# openysy.net
KiCad netlist of a schematic drawn in EAGLE
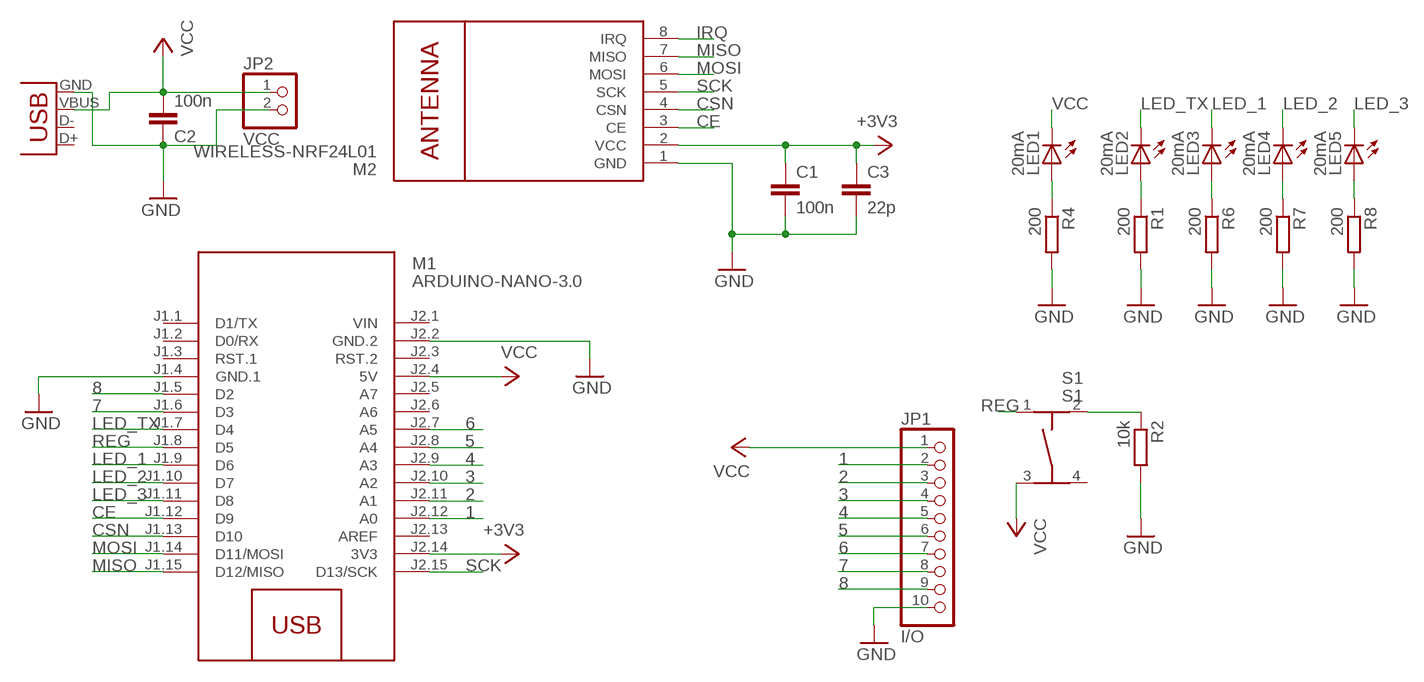
[diagram p0: schematic, sheet 1]

(export (version "E")
  (design (tool "Eeschema 10.0.6"))
  (components
    (comp (ref "C1")
      (value "100n")
      (footprint "eagle-import:C1206")
      (libsource (lib "eagle-import") (part "C-EUC1206"))
    )
    (comp (ref "C2")
      (value "100n")
      (footprint "eagle-import:C1206")
      (libsource (lib "eagle-import") (part "C-EUC1206"))
    )
    (comp (ref "C3")
      (value "22p")
      (footprint "eagle-import:C1206")
      (libsource (lib "eagle-import") (part "C-EUC1206"))
    )
    (comp (ref "JP1")
      (value "I/O")
      (footprint "eagle-import:1X10")
      (libsource (lib "eagle-import") (part "PINHD-1X10"))
    )
    (comp (ref "JP2")
      (value "VCC")
      (footprint "eagle-import:1X02")
      (libsource (lib "eagle-import") (part "PINHD-1X2"))
    )
    (comp (ref "LED1")
      (value "20mA")
      (footprint "eagle-import:CHIPLED_1206")
      (libsource (lib "eagle-import") (part "LEDCHIPLED_1206"))
    )
    (comp (ref "LED2")
      (value "20mA")
      (footprint "eagle-import:CHIPLED_1206")
      (libsource (lib "eagle-import") (part "LEDCHIPLED_1206"))
    )
    (comp (ref "LED3")
      (value "20mA")
      (footprint "eagle-import:CHIPLED_1206")
      (libsource (lib "eagle-import") (part "LEDCHIPLED_1206"))
    )
    (comp (ref "LED4")
      (value "20mA")
      (footprint "eagle-import:CHIPLED_1206")
      (libsource (lib "eagle-import") (part "LEDCHIPLED_1206"))
    )
    (comp (ref "LED5")
      (value "20mA")
      (footprint "eagle-import:CHIPLED_1206")
      (libsource (lib "eagle-import") (part "LEDCHIPLED_1206"))
    )
    (comp (ref "M1")
      (value "ARDUINO-NANO-3.0")
      (footprint "eagle-import:ARDUINO-NANO-3.0")
      (libsource (lib "eagle-import") (part "ARDUINO-NANO-3.0"))
    )
    (comp (ref "M2")
      (value "WIRELESS-NRF24L01")
      (footprint "eagle-import:WIRELESS-NRF24L01")
      (libsource (lib "eagle-import") (part "WIRELESS-NRF24L01"))
    )
    (comp (ref "R1")
      (value "200")
      (footprint "eagle-import:R1206")
      (libsource (lib "eagle-import") (part "R-EU_R1206"))
    )
    (comp (ref "R2")
      (value "10k")
      (footprint "eagle-import:R1206")
      (libsource (lib "eagle-import") (part "R-EU_R1206"))
    )
    (comp (ref "R4")
      (value "200")
      (footprint "eagle-import:R1206")
      (libsource (lib "eagle-import") (part "R-EU_R1206"))
    )
    (comp (ref "R6")
      (value "200")
      (footprint "eagle-import:R1206")
      (libsource (lib "eagle-import") (part "R-EU_R1206"))
    )
    (comp (ref "R7")
      (value "200")
      (footprint "eagle-import:R1206")
      (libsource (lib "eagle-import") (part "R-EU_R1206"))
    )
    (comp (ref "R8")
      (value "200")
      (footprint "eagle-import:R1206")
      (libsource (lib "eagle-import") (part "R-EU_R1206"))
    )
    (comp (ref "S1")
      (value "S1")
      (footprint "eagle-import:TASTER-9314_SMD")
      (libsource (lib "eagle-import") (part "TASTER-9314_SMD"))
    )
    (comp (ref "X2")
      (value "USBPTH")
      (footprint "eagle-import:USB-B-PTH")
      (libsource (lib "eagle-import") (part "USBPTH"))
    )
  )
  (nets
    (net (code "1") (name "+3V3") (class "Default")
      (node (ref "C1") (pin "1") (pinfunction "1_1") (pintype "passive"))
      (node (ref "C3") (pin "1") (pinfunction "1_1") (pintype "passive"))
      (node (ref "M1") (pin "J2.14") (pinfunction "3V3_J2.14") (pintype "power_in"))
      (node (ref "M2") (pin "2") (pinfunction "VCC_2") (pintype "power_in"))
    )
    (net (code "2") (name "/1") (class "Default")
      (node (ref "JP1") (pin "2") (pinfunction "2_2") (pintype "passive"))
      (node (ref "M1") (pin "J2.12") (pinfunction "A0_J2.12") (pintype "bidirectional"))
    )
    (net (code "3") (name "/2") (class "Default")
      (node (ref "JP1") (pin "3") (pinfunction "3_3") (pintype "passive"))
      (node (ref "M1") (pin "J2.11") (pinfunction "A1_J2.11") (pintype "bidirectional"))
    )
    (net (code "4") (name "/3") (class "Default")
      (node (ref "JP1") (pin "4") (pinfunction "4_4") (pintype "passive"))
      (node (ref "M1") (pin "J2.10") (pinfunction "A2_J2.10") (pintype "bidirectional"))
    )
    (net (code "5") (name "/4") (class "Default")
      (node (ref "JP1") (pin "5") (pinfunction "5_5") (pintype "passive"))
      (node (ref "M1") (pin "J2.9") (pinfunction "A3_J2.9") (pintype "bidirectional"))
    )
    (net (code "6") (name "/5") (class "Default")
      (node (ref "JP1") (pin "6") (pinfunction "6_6") (pintype "passive"))
      (node (ref "M1") (pin "J2.8") (pinfunction "A4_J2.8") (pintype "bidirectional"))
    )
    (net (code "7") (name "/6") (class "Default")
      (node (ref "JP1") (pin "7") (pinfunction "7_7") (pintype "passive"))
      (node (ref "M1") (pin "J2.7") (pinfunction "A5_J2.7") (pintype "bidirectional"))
    )
    (net (code "8") (name "/7") (class "Default")
      (node (ref "JP1") (pin "8") (pinfunction "8_8") (pintype "passive"))
      (node (ref "M1") (pin "J1.6") (pinfunction "D3_J1.6") (pintype "bidirectional"))
    )
    (net (code "9") (name "/8") (class "Default")
      (node (ref "JP1") (pin "9") (pinfunction "9_9") (pintype "passive"))
      (node (ref "M1") (pin "J1.5") (pinfunction "D2_J1.5") (pintype "bidirectional"))
    )
    (net (code "10") (name "/CE") (class "Default")
      (node (ref "M1") (pin "J1.12") (pinfunction "D9_J1.12") (pintype "bidirectional"))
      (node (ref "M2") (pin "3") (pinfunction "CE_3") (pintype "bidirectional"))
    )
    (net (code "11") (name "/CSN") (class "Default")
      (node (ref "M1") (pin "J1.13") (pinfunction "D10_J1.13") (pintype "bidirectional"))
      (node (ref "M2") (pin "4") (pinfunction "CSN_4") (pintype "bidirectional"))
    )
    (net (code "12") (name "/IRQ") (class "Default")
      (node (ref "M2") (pin "8") (pinfunction "IRQ_8") (pintype "bidirectional"))
    )
    (net (code "13") (name "/LED_1") (class "Default")
      (node (ref "LED3") (pin "C") (pinfunction "C_C") (pintype "passive"))
      (node (ref "M1") (pin "J1.9") (pinfunction "D6_J1.9") (pintype "bidirectional"))
    )
    (net (code "14") (name "/LED_2") (class "Default")
      (node (ref "LED4") (pin "C") (pinfunction "C_C") (pintype "passive"))
      (node (ref "M1") (pin "J1.10") (pinfunction "D7_J1.10") (pintype "bidirectional"))
    )
    (net (code "15") (name "/LED_3") (class "Default")
      (node (ref "LED5") (pin "C") (pinfunction "C_C") (pintype "passive"))
      (node (ref "M1") (pin "J1.11") (pinfunction "D8_J1.11") (pintype "bidirectional"))
    )
    (net (code "16") (name "/LED_TX") (class "Default")
      (node (ref "LED2") (pin "C") (pinfunction "C_C") (pintype "passive"))
      (node (ref "M1") (pin "J1.7") (pinfunction "D4_J1.7") (pintype "bidirectional"))
    )
    (net (code "17") (name "/MISO") (class "Default")
      (node (ref "M1") (pin "J1.15") (pinfunction "D12/MISO_J1.15") (pintype "bidirectional"))
      (node (ref "M2") (pin "7") (pinfunction "MISO_7") (pintype "bidirectional"))
    )
    (net (code "18") (name "/MOSI") (class "Default")
      (node (ref "M1") (pin "J1.14") (pinfunction "D11/MOSI_J1.14") (pintype "bidirectional"))
      (node (ref "M2") (pin "6") (pinfunction "MOSI_6") (pintype "bidirectional"))
    )
    (net (code "19") (name "/REG") (class "Default")
      (node (ref "M1") (pin "J1.8") (pinfunction "D5_J1.8") (pintype "bidirectional"))
      (node (ref "S1") (pin "1") (pinfunction "1_1") (pintype "passive"))
    )
    (net (code "20") (name "/SCK") (class "Default")
      (node (ref "M1") (pin "J2.15") (pinfunction "D13/SCK_J2.15") (pintype "bidirectional"))
      (node (ref "M2") (pin "5") (pinfunction "SCK_5") (pintype "bidirectional"))
    )
    (net (code "21") (name "/VIN") (class "Default")
      (node (ref "M1") (pin "J2.1") (pinfunction "VIN_J2.1") (pintype "power_in"))
    )
    (net (code "22") (name "GND") (class "Default")
      (node (ref "C1") (pin "2") (pinfunction "2_2") (pintype "passive"))
      (node (ref "C2") (pin "1") (pinfunction "1_1") (pintype "passive"))
      (node (ref "C3") (pin "2") (pinfunction "2_2") (pintype "passive"))
      (node (ref "JP1") (pin "10") (pinfunction "10_10") (pintype "passive"))
      (node (ref "JP2") (pin "2") (pinfunction "2_2") (pintype "passive"))
      (node (ref "M1") (pin "J1.4") (pinfunction "GND.1_J1.4") (pintype "power_in"))
      (node (ref "M1") (pin "J2.2") (pinfunction "GND.2_J2.2") (pintype "power_in"))
      (node (ref "M2") (pin "1") (pinfunction "GND_1") (pintype "power_in"))
      (node (ref "R1") (pin "2") (pinfunction "2_2") (pintype "passive"))
      (node (ref "R2") (pin "2") (pinfunction "2_2") (pintype "passive"))
      (node (ref "R4") (pin "2") (pinfunction "2_2") (pintype "passive"))
      (node (ref "R6") (pin "2") (pinfunction "2_2") (pintype "passive"))
      (node (ref "R7") (pin "2") (pinfunction "2_2") (pintype "passive"))
      (node (ref "R8") (pin "2") (pinfunction "2_2") (pintype "passive"))
      (node (ref "X2") (pin "GND") (pinfunction "GND_GND") (pintype "bidirectional"))
    )
    (net (code "23") (name "Net-(LED1-PadA)") (class "Default")
      (node (ref "LED1") (pin "A") (pinfunction "A_A") (pintype "passive"))
      (node (ref "R4") (pin "1") (pinfunction "1_1") (pintype "passive"))
    )
    (net (code "24") (name "Net-(LED2-PadA)") (class "Default")
      (node (ref "LED2") (pin "A") (pinfunction "A_A") (pintype "passive"))
      (node (ref "R1") (pin "1") (pinfunction "1_1") (pintype "passive"))
    )
    (net (code "25") (name "Net-(LED3-PadA)") (class "Default")
      (node (ref "LED3") (pin "A") (pinfunction "A_A") (pintype "passive"))
      (node (ref "R6") (pin "1") (pinfunction "1_1") (pintype "passive"))
    )
    (net (code "26") (name "Net-(LED4-PadA)") (class "Default")
      (node (ref "LED4") (pin "A") (pinfunction "A_A") (pintype "passive"))
      (node (ref "R7") (pin "1") (pinfunction "1_1") (pintype "passive"))
    )
    (net (code "27") (name "Net-(LED5-PadA)") (class "Default")
      (node (ref "LED5") (pin "A") (pinfunction "A_A") (pintype "passive"))
      (node (ref "R8") (pin "1") (pinfunction "1_1") (pintype "passive"))
    )
    (net (code "28") (name "Net-(R2-Pad1)") (class "Default")
      (node (ref "R2") (pin "1") (pinfunction "1_1") (pintype "passive"))
      (node (ref "S1") (pin "2") (pinfunction "2_2") (pintype "passive"))
    )
    (net (code "29") (name "VCC") (class "Default")
      (node (ref "C2") (pin "2") (pinfunction "2_2") (pintype "passive"))
      (node (ref "JP1") (pin "1") (pinfunction "1_1") (pintype "passive"))
      (node (ref "JP2") (pin "1") (pinfunction "1_1") (pintype "passive"))
      (node (ref "LED1") (pin "C") (pinfunction "C_C") (pintype "passive"))
      (node (ref "M1") (pin "J2.4") (pinfunction "5V_J2.4") (pintype "power_in"))
      (node (ref "S1") (pin "3") (pinfunction "3_3") (pintype "passive"))
      (node (ref "X2") (pin "VBUS") (pinfunction "VBUS_VBUS") (pintype "bidirectional"))
    )
    (net (code "30") (name "unconnected-(M1-A6-PadJ2.6)") (class "Default")
      (node (ref "M1") (pin "J2.6") (pinfunction "A6_J2.6") (pintype "bidirectional"))
    )
    (net (code "31") (name "unconnected-(M1-A7-PadJ2.5)") (class "Default")
      (node (ref "M1") (pin "J2.5") (pinfunction "A7_J2.5") (pintype "bidirectional"))
    )
    (net (code "32") (name "unconnected-(M1-AREF-PadJ2.13)") (class "Default")
      (node (ref "M1") (pin "J2.13") (pinfunction "AREF_J2.13") (pintype "bidirectional"))
    )
    (net (code "33") (name "unconnected-(M1-D0{slash}RX-PadJ1.2)") (class "Default")
      (node (ref "M1") (pin "J1.2") (pinfunction "D0/RX_J1.2") (pintype "bidirectional"))
    )
    (net (code "34") (name "unconnected-(M1-D1{slash}TX-PadJ1.1)") (class "Default")
      (node (ref "M1") (pin "J1.1") (pinfunction "D1/TX_J1.1") (pintype "bidirectional"))
    )
    (net (code "35") (name "unconnected-(M1-RST.1-PadJ1.3)") (class "Default")
      (node (ref "M1") (pin "J1.3") (pinfunction "RST.1_J1.3") (pintype "bidirectional"))
    )
    (net (code "36") (name "unconnected-(M1-RST.2-PadJ2.3)") (class "Default")
      (node (ref "M1") (pin "J2.3") (pinfunction "RST.2_J2.3") (pintype "bidirectional"))
    )
    (net (code "37") (name "unconnected-(S1-Pad4)") (class "Default")
      (node (ref "S1") (pin "4") (pinfunction "4_4") (pintype "passive"))
    )
    (net (code "38") (name "unconnected-(X2-PadD+)") (class "Default")
      (node (ref "X2") (pin "D+") (pinfunction "D+_D+") (pintype "bidirectional"))
    )
    (net (code "39") (name "unconnected-(X2-PadD-)") (class "Default")
      (node (ref "X2") (pin "D-") (pinfunction "D-_D-") (pintype "bidirectional"))
    )
  )
)
